# IoTKitV3th.net
KiCad netlist of a schematic drawn in EAGLE
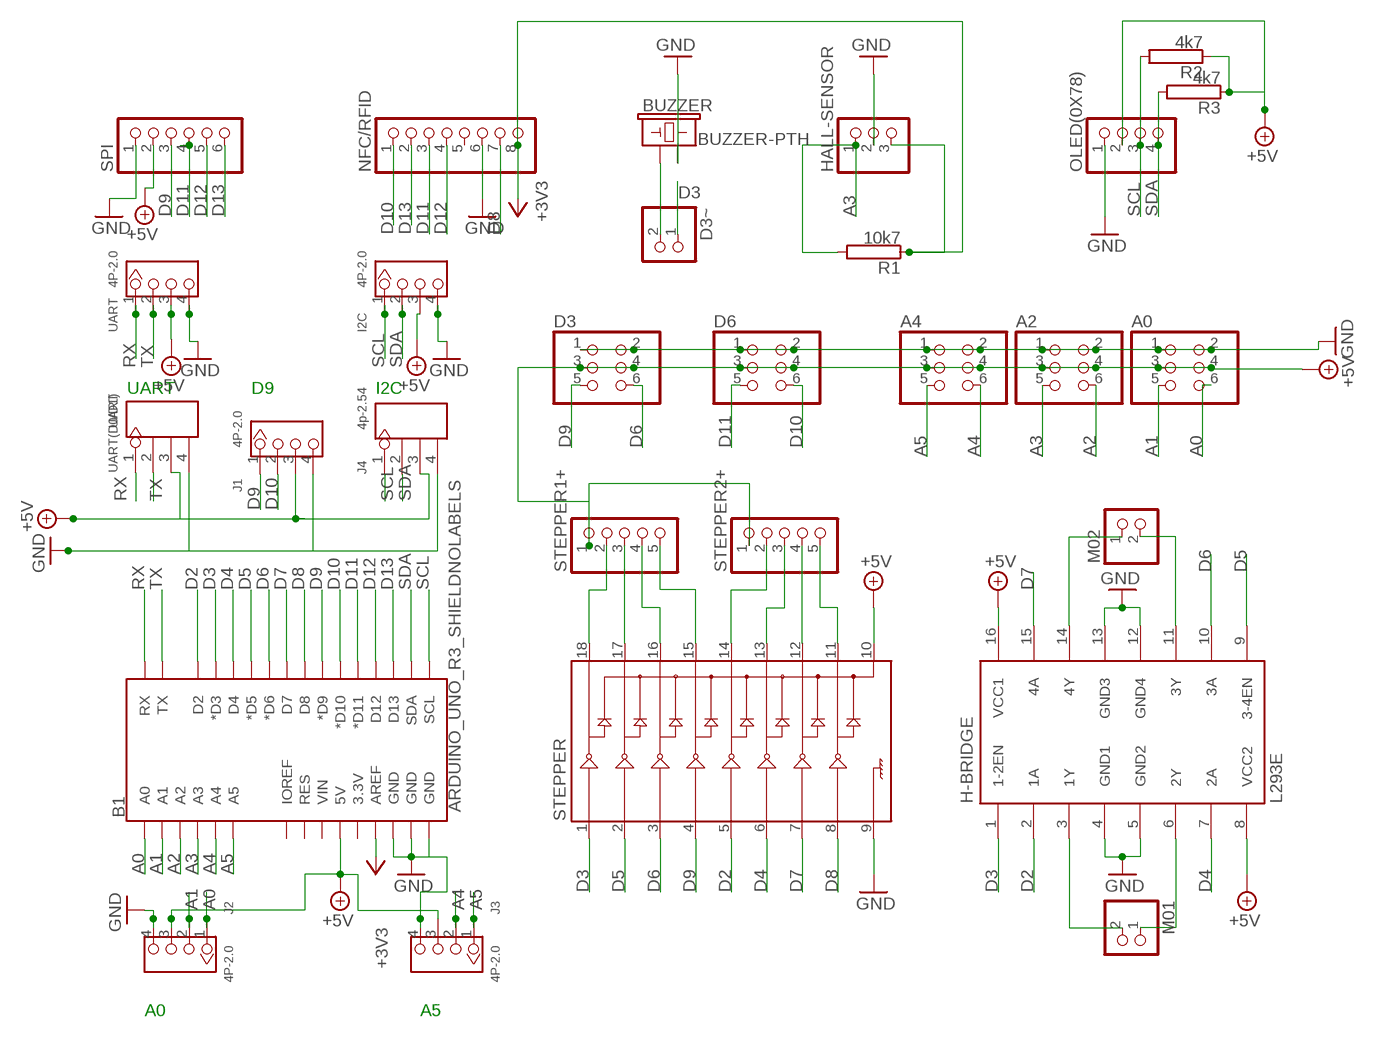
[diagram p0: schematic, sheet 1]

(export (version "E")
  (design (tool "Eeschema 10.0.6"))
  (components
    (comp (ref "A0")
      (value "PINHD-2X3")
      (footprint "eagle-import:2X03")
      (libsource (lib "eagle-import") (part "PINHD-2X3"))
    )
    (comp (ref "A2")
      (value "PINHD-2X3")
      (footprint "eagle-import:2X03")
      (libsource (lib "eagle-import") (part "PINHD-2X3"))
    )
    (comp (ref "A4")
      (value "PINHD-2X3")
      (footprint "eagle-import:2X03")
      (libsource (lib "eagle-import") (part "PINHD-2X3"))
    )
    (comp (ref "B1")
      (value "ARDUINO_UNO_R3_SHIELDNOLABELS")
      (footprint "eagle-import:UNO_R3_SHIELD_NOLABELS")
      (libsource (lib "eagle-import") (part "ARDUINO_UNO_R3_SHIELDNOLABELS"))
    )
    (comp (ref "BUZZER")
      (value "BUZZER-PTH")
      (footprint "eagle-import:BUZZER-12MM")
      (libsource (lib "eagle-import") (part "BUZZER-PTH"))
    )
    (comp (ref "D3")
      (value "PINHD-2X3")
      (footprint "eagle-import:2X03")
      (libsource (lib "eagle-import") (part "PINHD-2X3"))
    )
    (comp (ref "D3~")
      (value "PINHD-1X2")
      (footprint "eagle-import:1X02")
      (libsource (lib "eagle-import") (part "PINHD-1X2"))
    )
    (comp (ref "D6")
      (value "PINHD-2X3")
      (footprint "eagle-import:2X03")
      (libsource (lib "eagle-import") (part "PINHD-2X3"))
    )
    (comp (ref "H-BRIDGE")
      (value "L293E")
      (footprint "eagle-import:DIL16")
      (fields (field (name "MF") "Arrow Electronics"))
      (libsource (lib "eagle-import") (part "L293E"))
    )
    (comp (ref "HALL-SENSOR")
      (value "PINHD-1X3")
      (footprint "eagle-import:1X03")
      (libsource (lib "eagle-import") (part "PINHD-1X3"))
    )
    (comp (ref "I2C")
      (value "4P-2.0")
      (footprint "eagle-import:HW4-2.0")
      (libsource (lib "eagle-import") (part "GROVE-CONNECTOR-DIP(4P-2.0)"))
    )
    (comp (ref "J1")
      (value "4P-2.0")
      (footprint "eagle-import:HW4-2.0")
      (libsource (lib "eagle-import") (part "GROVE-CONNECTOR-DIP(4P-2.0)"))
    )
    (comp (ref "J2")
      (value "4P-2.0")
      (footprint "eagle-import:HW4-2.0")
      (libsource (lib "eagle-import") (part "GROVE-CONNECTOR-DIP(4P-2.0)"))
    )
    (comp (ref "J3")
      (value "4P-2.0")
      (footprint "eagle-import:HW4-2.0")
      (libsource (lib "eagle-import") (part "GROVE-CONNECTOR-DIP(4P-2.0)"))
    )
    (comp (ref "J4")
      (value "4p-2.54")
      (footprint "eagle-import:H4-2.54")
      (fields (field (name "MPN") "P125-1104A0BS116A1"))
      (libsource (lib "eagle-import") (part "DIP-BLACK-MALE-HEADER-VERT(4P-2.54)"))
    )
    (comp (ref "M01")
      (value "PINHD-1X2")
      (footprint "eagle-import:1X02")
      (libsource (lib "eagle-import") (part "PINHD-1X2"))
    )
    (comp (ref "M02")
      (value "PINHD-1X2")
      (footprint "eagle-import:1X02")
      (libsource (lib "eagle-import") (part "PINHD-1X2"))
    )
    (comp (ref "NFC/RFID")
      (value "PINHD-1X8")
      (footprint "eagle-import:1X08")
      (libsource (lib "eagle-import") (part "PINHD-1X8"))
    )
    (comp (ref "OLED(0X78)")
      (value "PINHD-1X4")
      (footprint "eagle-import:1X04")
      (libsource (lib "eagle-import") (part "PINHD-1X4"))
    )
    (comp (ref "R1")
      (value "10k7")
      (footprint "eagle-import:CA0001")
      (libsource (lib "eagle-import") (part "RCA0001"))
    )
    (comp (ref "R2")
      (value "4k7")
      (footprint "eagle-import:CA0001")
      (libsource (lib "eagle-import") (part "RCA0001"))
    )
    (comp (ref "R3")
      (value "4k7")
      (footprint "eagle-import:CA0001")
      (libsource (lib "eagle-import") (part "RCA0001"))
    )
    (comp (ref "SPI")
      (value "PINHD-1X6")
      (footprint "eagle-import:1X06")
      (libsource (lib "eagle-import") (part "PINHD-1X6"))
    )
    (comp (ref "STEPPER")
      (value "ULN2803DIP")
      (footprint "eagle-import:DIL18")
      (libsource (lib "eagle-import") (part "ULN2803DIP"))
    )
    (comp (ref "STEPPER1+")
      (value "PINHD-1X5")
      (footprint "eagle-import:1X05")
      (libsource (lib "eagle-import") (part "PINHD-1X5"))
    )
    (comp (ref "STEPPER2+")
      (value "PINHD-1X5")
      (footprint "eagle-import:1X05")
      (libsource (lib "eagle-import") (part "PINHD-1X5"))
    )
    (comp (ref "UART")
      (value "4P-2.0")
      (footprint "eagle-import:HW4-2.0")
      (libsource (lib "eagle-import") (part "GROVE-CONNECTOR-DIP(4P-2.0)"))
    )
    (comp (ref "UART(D0/D1)")
      (value "UART")
      (footprint "eagle-import:H4-2.54")
      (fields (field (name "MPN") "P125-1104A0BS116A1"))
      (libsource (lib "eagle-import") (part "DIP-BLACK-MALE-HEADER-VERT(4P-2.54)"))
    )
  )
  (nets
    (net (code "1") (name "+3V3") (class "Default")
      (node (ref "B1") (pin "AREF") (pinfunction "AREF_AREF") (pintype "bidirectional"))
      (node (ref "HALL-SENSOR") (pin "3") (pinfunction "3_3") (pintype "passive"))
      (node (ref "NFC/RFID") (pin "8") (pinfunction "8_8") (pintype "passive"))
      (node (ref "R1") (pin "1") (pinfunction "1_1") (pintype "passive"))
    )
    (net (code "2") (name "+5V") (class "Default")
      (node (ref "A0") (pin "3") (pinfunction "3_3") (pintype "passive"))
      (node (ref "A0") (pin "4") (pinfunction "4_4") (pintype "passive"))
      (node (ref "A2") (pin "3") (pinfunction "3_3") (pintype "passive"))
      (node (ref "A2") (pin "4") (pinfunction "4_4") (pintype "passive"))
      (node (ref "A4") (pin "3") (pinfunction "3_3") (pintype "passive"))
      (node (ref "A4") (pin "4") (pinfunction "4_4") (pintype "passive"))
      (node (ref "B1") (pin "5V") (pinfunction "5V_5V") (pintype "bidirectional"))
      (node (ref "D3") (pin "3") (pinfunction "3_3") (pintype "passive"))
      (node (ref "D3") (pin "4") (pinfunction "4_4") (pintype "passive"))
      (node (ref "D6") (pin "3") (pinfunction "3_3") (pintype "passive"))
      (node (ref "D6") (pin "4") (pinfunction "4_4") (pintype "passive"))
      (node (ref "H-BRIDGE") (pin "16") (pinfunction "VCC1_16") (pintype "power_in"))
      (node (ref "H-BRIDGE") (pin "8") (pinfunction "VCC2_8") (pintype "power_in"))
      (node (ref "I2C") (pin "3") (pinfunction "3_3") (pintype "bidirectional"))
      (node (ref "J1") (pin "3") (pinfunction "3_3") (pintype "bidirectional"))
      (node (ref "J2") (pin "3") (pinfunction "3_3") (pintype "bidirectional"))
      (node (ref "J3") (pin "3") (pinfunction "3_3") (pintype "bidirectional"))
      (node (ref "J4") (pin "3") (pinfunction "P$3_3") (pintype "bidirectional"))
      (node (ref "OLED(0X78)") (pin "2") (pinfunction "2_2") (pintype "passive"))
      (node (ref "R2") (pin "1") (pinfunction "1_1") (pintype "passive"))
      (node (ref "R3") (pin "1") (pinfunction "1_1") (pintype "passive"))
      (node (ref "SPI") (pin "2") (pinfunction "2_2") (pintype "passive"))
      (node (ref "STEPPER") (pin "10") (pinfunction "10_10") (pintype "bidirectional"))
      (node (ref "STEPPER1+") (pin "1") (pinfunction "1_1") (pintype "passive"))
      (node (ref "STEPPER2+") (pin "1") (pinfunction "1_1") (pintype "passive"))
      (node (ref "UART") (pin "3") (pinfunction "3_3") (pintype "bidirectional"))
      (node (ref "UART(D0/D1)") (pin "3") (pinfunction "P$3_3") (pintype "bidirectional"))
    )
    (net (code "3") (name "/A0") (class "Default")
      (node (ref "A0") (pin "6") (pinfunction "6_6") (pintype "passive"))
      (node (ref "B1") (pin "A0") (pinfunction "A0_A0") (pintype "bidirectional"))
      (node (ref "J2") (pin "1") (pinfunction "1_1") (pintype "bidirectional"))
    )
    (net (code "4") (name "/A1") (class "Default")
      (node (ref "A0") (pin "5") (pinfunction "5_5") (pintype "passive"))
      (node (ref "B1") (pin "A1") (pinfunction "A1_A1") (pintype "bidirectional"))
      (node (ref "J2") (pin "2") (pinfunction "2_2") (pintype "bidirectional"))
    )
    (net (code "5") (name "/A2") (class "Default")
      (node (ref "A2") (pin "6") (pinfunction "6_6") (pintype "passive"))
      (node (ref "B1") (pin "A2") (pinfunction "A2_A2") (pintype "bidirectional"))
    )
    (net (code "6") (name "/A3") (class "Default")
      (node (ref "A2") (pin "5") (pinfunction "5_5") (pintype "passive"))
      (node (ref "B1") (pin "A3") (pinfunction "A3_A3") (pintype "bidirectional"))
      (node (ref "HALL-SENSOR") (pin "1") (pinfunction "1_1") (pintype "passive"))
      (node (ref "R1") (pin "2") (pinfunction "2_2") (pintype "passive"))
    )
    (net (code "7") (name "/A4") (class "Default")
      (node (ref "A4") (pin "6") (pinfunction "6_6") (pintype "passive"))
      (node (ref "B1") (pin "A4") (pinfunction "A4_A4") (pintype "bidirectional"))
      (node (ref "J3") (pin "2") (pinfunction "2_2") (pintype "bidirectional"))
    )
    (net (code "8") (name "/A5") (class "Default")
      (node (ref "A4") (pin "5") (pinfunction "5_5") (pintype "passive"))
      (node (ref "B1") (pin "A5") (pinfunction "A5_A5") (pintype "bidirectional"))
      (node (ref "J3") (pin "1") (pinfunction "1_1") (pintype "bidirectional"))
    )
    (net (code "9") (name "/D2") (class "Default")
      (node (ref "B1") (pin "D2") (pinfunction "D2_D2") (pintype "bidirectional"))
      (node (ref "H-BRIDGE") (pin "2") (pinfunction "1A_2") (pintype "input"))
      (node (ref "STEPPER") (pin "5") (pinfunction "5_5") (pintype "bidirectional"))
    )
    (net (code "10") (name "/D3") (class "Default")
      (node (ref "B1") (pin "D3") (pinfunction "*D3_D3") (pintype "bidirectional"))
      (node (ref "D3~") (pin "1") (pinfunction "1_1") (pintype "passive"))
      (node (ref "H-BRIDGE") (pin "1") (pinfunction "1-2EN_1") (pintype "input"))
      (node (ref "STEPPER") (pin "1") (pinfunction "1_1") (pintype "bidirectional"))
    )
    (net (code "11") (name "/D4") (class "Default")
      (node (ref "B1") (pin "D4") (pinfunction "D4_D4") (pintype "bidirectional"))
      (node (ref "H-BRIDGE") (pin "7") (pinfunction "2A_7") (pintype "input"))
      (node (ref "STEPPER") (pin "6") (pinfunction "6_6") (pintype "bidirectional"))
    )
    (net (code "12") (name "/D5") (class "Default")
      (node (ref "B1") (pin "D5") (pinfunction "*D5_D5") (pintype "bidirectional"))
      (node (ref "H-BRIDGE") (pin "9") (pinfunction "3-4EN_9") (pintype "input"))
      (node (ref "STEPPER") (pin "2") (pinfunction "2_2") (pintype "bidirectional"))
    )
    (net (code "13") (name "/D6") (class "Default")
      (node (ref "B1") (pin "D6") (pinfunction "*D6_D6") (pintype "bidirectional"))
      (node (ref "D3") (pin "6") (pinfunction "6_6") (pintype "passive"))
      (node (ref "H-BRIDGE") (pin "10") (pinfunction "3A_10") (pintype "input"))
      (node (ref "STEPPER") (pin "3") (pinfunction "3_3") (pintype "bidirectional"))
    )
    (net (code "14") (name "/D7") (class "Default")
      (node (ref "B1") (pin "D7") (pinfunction "D7_D7") (pintype "bidirectional"))
      (node (ref "H-BRIDGE") (pin "15") (pinfunction "4A_15") (pintype "input"))
      (node (ref "STEPPER") (pin "7") (pinfunction "7_7") (pintype "bidirectional"))
    )
    (net (code "15") (name "/D8") (class "Default")
      (node (ref "B1") (pin "D8") (pinfunction "D8_D8") (pintype "bidirectional"))
      (node (ref "NFC/RFID") (pin "7") (pinfunction "7_7") (pintype "passive"))
      (node (ref "STEPPER") (pin "8") (pinfunction "8_8") (pintype "bidirectional"))
    )
    (net (code "16") (name "/D9") (class "Default")
      (node (ref "B1") (pin "D9") (pinfunction "*D9_D9") (pintype "bidirectional"))
      (node (ref "D3") (pin "5") (pinfunction "5_5") (pintype "passive"))
      (node (ref "J1") (pin "1") (pinfunction "1_1") (pintype "bidirectional"))
      (node (ref "SPI") (pin "3") (pinfunction "3_3") (pintype "passive"))
      (node (ref "STEPPER") (pin "4") (pinfunction "4_4") (pintype "bidirectional"))
    )
    (net (code "17") (name "/D10") (class "Default")
      (node (ref "B1") (pin "D10") (pinfunction "*D10_D10") (pintype "bidirectional"))
      (node (ref "D6") (pin "6") (pinfunction "6_6") (pintype "passive"))
      (node (ref "J1") (pin "2") (pinfunction "2_2") (pintype "bidirectional"))
      (node (ref "NFC/RFID") (pin "1") (pinfunction "1_1") (pintype "passive"))
    )
    (net (code "18") (name "/D11") (class "Default")
      (node (ref "B1") (pin "D11") (pinfunction "*D11_D11") (pintype "bidirectional"))
      (node (ref "D6") (pin "5") (pinfunction "5_5") (pintype "passive"))
      (node (ref "NFC/RFID") (pin "3") (pinfunction "3_3") (pintype "passive"))
      (node (ref "SPI") (pin "4") (pinfunction "4_4") (pintype "passive"))
    )
    (net (code "19") (name "/D12") (class "Default")
      (node (ref "B1") (pin "D12") (pinfunction "D12_D12") (pintype "bidirectional"))
      (node (ref "NFC/RFID") (pin "4") (pinfunction "4_4") (pintype "passive"))
      (node (ref "SPI") (pin "5") (pinfunction "5_5") (pintype "passive"))
    )
    (net (code "20") (name "/D13") (class "Default")
      (node (ref "B1") (pin "D13") (pinfunction "D13_D13") (pintype "bidirectional"))
      (node (ref "NFC/RFID") (pin "2") (pinfunction "2_2") (pintype "passive"))
      (node (ref "SPI") (pin "6") (pinfunction "6_6") (pintype "passive"))
    )
    (net (code "21") (name "/RX") (class "Default")
      (node (ref "B1") (pin "RX") (pinfunction "RX_RX") (pintype "bidirectional"))
      (node (ref "UART") (pin "1") (pinfunction "1_1") (pintype "bidirectional"))
      (node (ref "UART(D0/D1)") (pin "1") (pinfunction "P$1_1") (pintype "bidirectional"))
    )
    (net (code "22") (name "/SCL") (class "Default")
      (node (ref "B1") (pin "SCL") (pinfunction "SCL_SCL") (pintype "bidirectional"))
      (node (ref "I2C") (pin "1") (pinfunction "1_1") (pintype "bidirectional"))
      (node (ref "J4") (pin "1") (pinfunction "P$1_1") (pintype "bidirectional"))
      (node (ref "OLED(0X78)") (pin "3") (pinfunction "3_3") (pintype "passive"))
      (node (ref "R2") (pin "2") (pinfunction "2_2") (pintype "passive"))
    )
    (net (code "23") (name "/SDA") (class "Default")
      (node (ref "B1") (pin "SDA") (pinfunction "SDA_SDA") (pintype "bidirectional"))
      (node (ref "I2C") (pin "2") (pinfunction "2_2") (pintype "bidirectional"))
      (node (ref "J4") (pin "2") (pinfunction "P$2_2") (pintype "bidirectional"))
      (node (ref "OLED(0X78)") (pin "4") (pinfunction "4_4") (pintype "passive"))
      (node (ref "R3") (pin "2") (pinfunction "2_2") (pintype "passive"))
    )
    (net (code "24") (name "/TX") (class "Default")
      (node (ref "B1") (pin "TX") (pinfunction "TX_TX") (pintype "bidirectional"))
      (node (ref "UART") (pin "2") (pinfunction "2_2") (pintype "bidirectional"))
      (node (ref "UART(D0/D1)") (pin "2") (pinfunction "P$2_2") (pintype "bidirectional"))
    )
    (net (code "25") (name "GND") (class "Default")
      (node (ref "A0") (pin "1") (pinfunction "1_1") (pintype "passive"))
      (node (ref "A0") (pin "2") (pinfunction "2_2") (pintype "passive"))
      (node (ref "A2") (pin "1") (pinfunction "1_1") (pintype "passive"))
      (node (ref "A2") (pin "2") (pinfunction "2_2") (pintype "passive"))
      (node (ref "A4") (pin "1") (pinfunction "1_1") (pintype "passive"))
      (node (ref "A4") (pin "2") (pinfunction "2_2") (pintype "passive"))
      (node (ref "B1") (pin "GND@0") (pinfunction "GND_GND@0") (pintype "bidirectional"))
      (node (ref "B1") (pin "GND@1") (pinfunction "GND_GND@1") (pintype "bidirectional"))
      (node (ref "B1") (pin "GND@2") (pinfunction "GND_GND@2") (pintype "bidirectional"))
      (node (ref "BUZZER") (pin "-") (pinfunction "2_-") (pintype "passive"))
      (node (ref "D3") (pin "1") (pinfunction "1_1") (pintype "passive"))
      (node (ref "D3") (pin "2") (pinfunction "2_2") (pintype "passive"))
      (node (ref "D6") (pin "1") (pinfunction "1_1") (pintype "passive"))
      (node (ref "D6") (pin "2") (pinfunction "2_2") (pintype "passive"))
      (node (ref "H-BRIDGE") (pin "12") (pinfunction "GND4_12") (pintype "power_in"))
      (node (ref "H-BRIDGE") (pin "13") (pinfunction "GND3_13") (pintype "power_in"))
      (node (ref "H-BRIDGE") (pin "4") (pinfunction "GND1_4") (pintype "power_in"))
      (node (ref "H-BRIDGE") (pin "5") (pinfunction "GND2_5") (pintype "power_in"))
      (node (ref "HALL-SENSOR") (pin "2") (pinfunction "2_2") (pintype "passive"))
      (node (ref "I2C") (pin "4") (pinfunction "4_4") (pintype "bidirectional"))
      (node (ref "J1") (pin "4") (pinfunction "4_4") (pintype "bidirectional"))
      (node (ref "J2") (pin "4") (pinfunction "4_4") (pintype "bidirectional"))
      (node (ref "J3") (pin "4") (pinfunction "4_4") (pintype "bidirectional"))
      (node (ref "J4") (pin "4") (pinfunction "P$4_4") (pintype "bidirectional"))
      (node (ref "NFC/RFID") (pin "6") (pinfunction "6_6") (pintype "passive"))
      (node (ref "OLED(0X78)") (pin "1") (pinfunction "1_1") (pintype "passive"))
      (node (ref "SPI") (pin "1") (pinfunction "1_1") (pintype "passive"))
      (node (ref "STEPPER") (pin "9") (pinfunction "9_9") (pintype "bidirectional"))
      (node (ref "UART") (pin "4") (pinfunction "4_4") (pintype "bidirectional"))
      (node (ref "UART(D0/D1)") (pin "4") (pinfunction "P$4_4") (pintype "bidirectional"))
    )
    (net (code "26") (name "Net-(BUZZER-1)") (class "Default")
      (node (ref "BUZZER") (pin "+") (pinfunction "1_+") (pintype "passive"))
      (node (ref "D3~") (pin "2") (pinfunction "2_2") (pintype "passive"))
    )
    (net (code "27") (name "Net-(H-BRIDGE-1Y)") (class "Default")
      (node (ref "H-BRIDGE") (pin "3") (pinfunction "1Y_3") (pintype "output"))
      (node (ref "M01") (pin "2") (pinfunction "2_2") (pintype "passive"))
    )
    (net (code "28") (name "Net-(H-BRIDGE-2Y)") (class "Default")
      (node (ref "H-BRIDGE") (pin "6") (pinfunction "2Y_6") (pintype "output"))
      (node (ref "M01") (pin "1") (pinfunction "1_1") (pintype "passive"))
    )
    (net (code "29") (name "Net-(H-BRIDGE-3Y)") (class "Default")
      (node (ref "H-BRIDGE") (pin "11") (pinfunction "3Y_11") (pintype "output"))
      (node (ref "M02") (pin "2") (pinfunction "2_2") (pintype "passive"))
    )
    (net (code "30") (name "Net-(H-BRIDGE-4Y)") (class "Default")
      (node (ref "H-BRIDGE") (pin "14") (pinfunction "4Y_14") (pintype "output"))
      (node (ref "M02") (pin "1") (pinfunction "1_1") (pintype "passive"))
    )
    (net (code "31") (name "Net-(STEPPER-Pad11)") (class "Default")
      (node (ref "STEPPER") (pin "11") (pinfunction "11_11") (pintype "bidirectional"))
      (node (ref "STEPPER2+") (pin "5") (pinfunction "5_5") (pintype "passive"))
    )
    (net (code "32") (name "Net-(STEPPER-Pad12)") (class "Default")
      (node (ref "STEPPER") (pin "12") (pinfunction "12_12") (pintype "bidirectional"))
      (node (ref "STEPPER2+") (pin "4") (pinfunction "4_4") (pintype "passive"))
    )
    (net (code "33") (name "Net-(STEPPER-Pad13)") (class "Default")
      (node (ref "STEPPER") (pin "13") (pinfunction "13_13") (pintype "bidirectional"))
      (node (ref "STEPPER2+") (pin "3") (pinfunction "3_3") (pintype "passive"))
    )
    (net (code "34") (name "Net-(STEPPER-Pad14)") (class "Default")
      (node (ref "STEPPER") (pin "14") (pinfunction "14_14") (pintype "bidirectional"))
      (node (ref "STEPPER2+") (pin "2") (pinfunction "2_2") (pintype "passive"))
    )
    (net (code "35") (name "Net-(STEPPER-Pad15)") (class "Default")
      (node (ref "STEPPER") (pin "15") (pinfunction "15_15") (pintype "bidirectional"))
      (node (ref "STEPPER1+") (pin "5") (pinfunction "5_5") (pintype "passive"))
    )
    (net (code "36") (name "Net-(STEPPER-Pad16)") (class "Default")
      (node (ref "STEPPER") (pin "16") (pinfunction "16_16") (pintype "bidirectional"))
      (node (ref "STEPPER1+") (pin "4") (pinfunction "4_4") (pintype "passive"))
    )
    (net (code "37") (name "Net-(STEPPER-Pad17)") (class "Default")
      (node (ref "STEPPER") (pin "17") (pinfunction "17_17") (pintype "bidirectional"))
      (node (ref "STEPPER1+") (pin "3") (pinfunction "3_3") (pintype "passive"))
    )
    (net (code "38") (name "Net-(STEPPER-Pad18)") (class "Default")
      (node (ref "STEPPER") (pin "18") (pinfunction "18_18") (pintype "bidirectional"))
      (node (ref "STEPPER1+") (pin "2") (pinfunction "2_2") (pintype "passive"))
    )
    (net (code "39") (name "unconnected-(B1-Pad3.3V)") (class "Default")
      (node (ref "B1") (pin "3.3V") (pinfunction "3.3V_3.3V") (pintype "bidirectional"))
    )
    (net (code "40") (name "unconnected-(B1-PadIOREF)") (class "Default")
      (node (ref "B1") (pin "IOREF") (pinfunction "IOREF_IOREF") (pintype "bidirectional"))
    )
    (net (code "41") (name "unconnected-(B1-PadRES)") (class "Default")
      (node (ref "B1") (pin "RES") (pinfunction "RES_RES") (pintype "bidirectional"))
    )
    (net (code "42") (name "unconnected-(B1-PadVIN)") (class "Default")
      (node (ref "B1") (pin "VIN") (pinfunction "VIN_VIN") (pintype "bidirectional"))
    )
    (net (code "43") (name "unconnected-(NFC/RFID-Pad5)") (class "Default")
      (node (ref "NFC/RFID") (pin "5") (pinfunction "5_5") (pintype "passive"))
    )
  )
)
